# pcuETH.net
KiCad netlist of a schematic drawn in Altium Designer
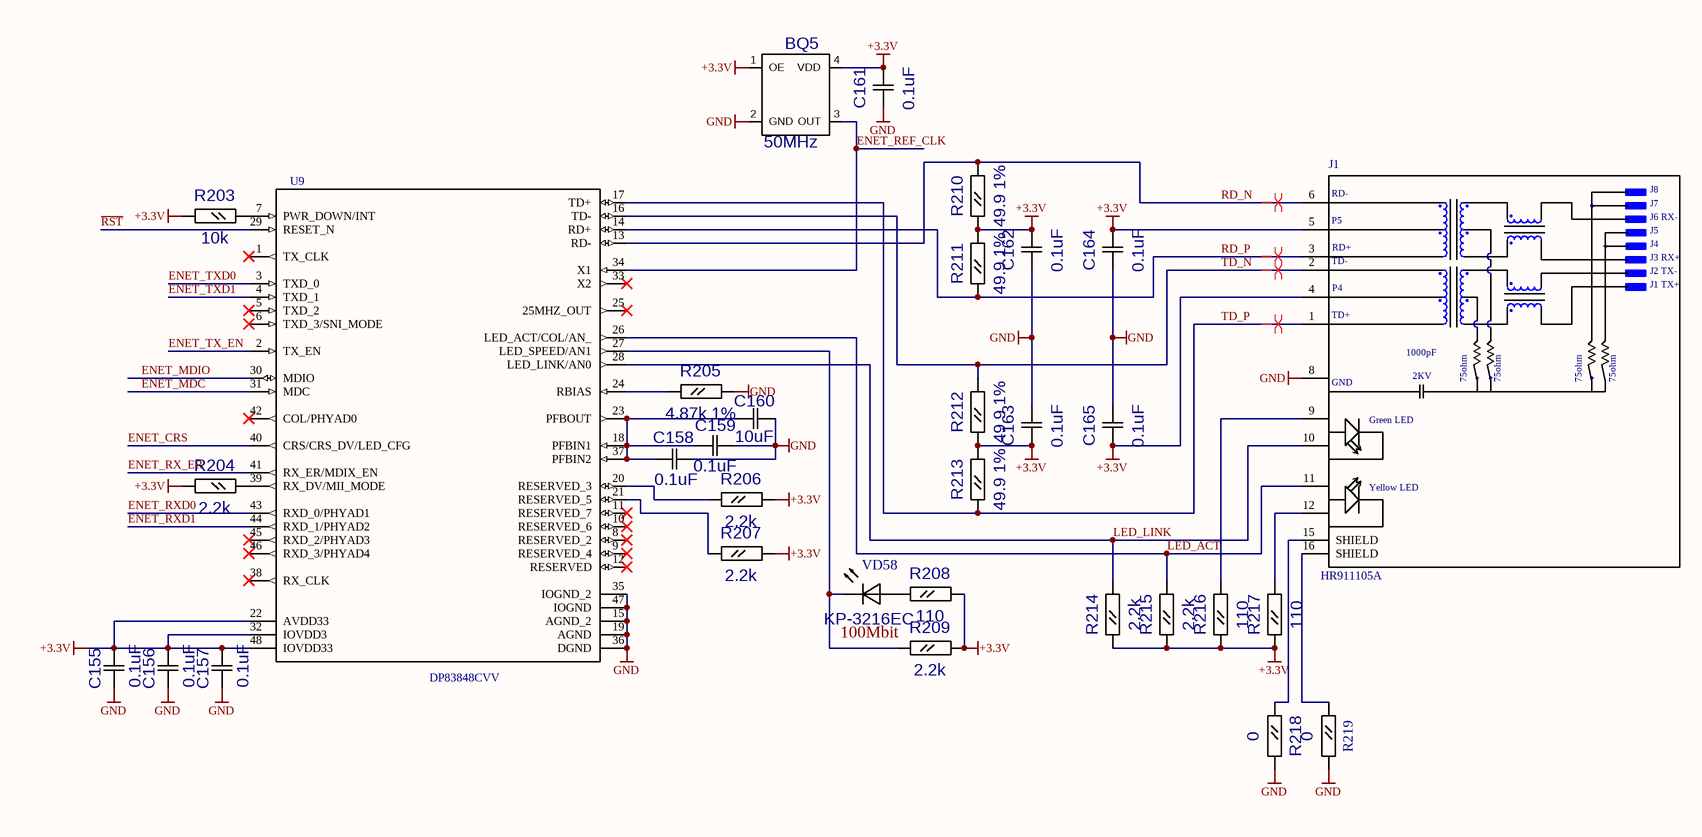
[diagram p0: pcuETH.SchDoc]

(export (version "E")
  (design (tool "Eeschema 10.0.6"))
  (components
    (comp (ref "BQ5") (value "50MHz") (footprint "FurmansLib:5032") (libsource (lib "Furmans") (part "OSC")))
    (comp (ref "C155")
      (value "0.1uF")
      (footprint "C0805")
      (description "C0805")
      (libsource (lib "FurmansLib") (part "C0805"))
    )
    (comp (ref "C156")
      (value "0.1uF")
      (footprint "C0805")
      (description "C0805")
      (libsource (lib "FurmansLib") (part "C0805"))
    )
    (comp (ref "C157")
      (value "0.1uF")
      (footprint "C0805")
      (description "C0805")
      (libsource (lib "FurmansLib") (part "C0805"))
    )
    (comp (ref "C158")
      (value "0.1uF")
      (footprint "C0805")
      (description "C0805")
      (libsource (lib "FurmansLib") (part "C0805"))
    )
    (comp (ref "C159")
      (value "0.1uF")
      (footprint "C0805")
      (description "C0805")
      (libsource (lib "FurmansLib") (part "C0805"))
    )
    (comp (ref "C160")
      (value "10uF")
      (footprint "C1206")
      (description "C1206")
      (libsource (lib "FurmansLib") (part "C1206"))
    )
    (comp (ref "C161")
      (value "0.1uF")
      (footprint "C0805")
      (description "C0805")
      (libsource (lib "FurmansLib") (part "C0805"))
    )
    (comp (ref "C162")
      (value "0.1uF")
      (footprint "C0805")
      (description "C0805")
      (libsource (lib "FurmansLib") (part "C0805"))
    )
    (comp (ref "C163")
      (value "0.1uF")
      (footprint "C0805")
      (description "C0805")
      (libsource (lib "FurmansLib") (part "C0805"))
    )
    (comp (ref "C164")
      (value "0.1uF")
      (footprint "C0805")
      (description "C0805")
      (libsource (lib "FurmansLib") (part "C0805"))
    )
    (comp (ref "C165")
      (value "0.1uF")
      (footprint "C0805")
      (description "C0805")
      (libsource (lib "FurmansLib") (part "C0805"))
    )
    (comp (ref "J1")
      (value "HR911105A")
      (footprint "HANRUN_HR911105A")
      (description "DIP RJ45 Connector;")
      (fields (field (name "MF") "HanRun"))
      (libsource (lib "FurmansLib") (part "HR911105A"))
    )
    (comp (ref "R203")
      (value "10k")
      (footprint "R0805")
      (description "R0805")
      (libsource (lib "FurmansLib") (part "R0805"))
    )
    (comp (ref "R204")
      (value "2.2k")
      (footprint "R0805")
      (description "R0805")
      (libsource (lib "FurmansLib") (part "R0805"))
    )
    (comp (ref "R205")
      (value "4.87k 1%")
      (footprint "R0805")
      (description "R0805")
      (libsource (lib "FurmansLib") (part "R0805"))
    )
    (comp (ref "R206")
      (value "2.2k")
      (footprint "R0805")
      (description "R0805")
      (libsource (lib "FurmansLib") (part "R0805"))
    )
    (comp (ref "R207")
      (value "2.2k")
      (footprint "R0805")
      (description "R0805")
      (libsource (lib "FurmansLib") (part "R0805"))
    )
    (comp (ref "R208")
      (value "110")
      (footprint "R0805")
      (description "R0805")
      (libsource (lib "FurmansLib") (part "R0805"))
    )
    (comp (ref "R209")
      (value "2.2k")
      (footprint "R0805")
      (description "R0805")
      (libsource (lib "FurmansLib") (part "R0805"))
    )
    (comp (ref "R210")
      (value "49.9 1%")
      (footprint "R0805")
      (description "R0805")
      (libsource (lib "FurmansLib") (part "R0805"))
    )
    (comp (ref "R211")
      (value "49.9 1%")
      (footprint "R0805")
      (description "R0805")
      (libsource (lib "FurmansLib") (part "R0805"))
    )
    (comp (ref "R212")
      (value "49.9 1%")
      (footprint "R0805")
      (description "R0805")
      (libsource (lib "FurmansLib") (part "R0805"))
    )
    (comp (ref "R213")
      (value "49.9 1%")
      (footprint "R0805")
      (description "R0805")
      (libsource (lib "FurmansLib") (part "R0805"))
    )
    (comp (ref "R214")
      (value "2.2k")
      (footprint "R0805")
      (description "R0805")
      (libsource (lib "FurmansLib") (part "R0805"))
    )
    (comp (ref "R215")
      (value "2.2k")
      (footprint "R0805")
      (description "R0805")
      (libsource (lib "FurmansLib") (part "R0805"))
    )
    (comp (ref "R216")
      (value "110")
      (footprint "R0805")
      (description "R0805")
      (libsource (lib "FurmansLib") (part "R0805"))
    )
    (comp (ref "R217")
      (value "110")
      (footprint "R0805")
      (description "R0805")
      (libsource (lib "FurmansLib") (part "R0805"))
    )
    (comp (ref "R218")
      (value "0")
      (footprint "R0805")
      (description "R0805")
      (libsource (lib "FurmansLib") (part "R0805"))
    )
    (comp (ref "R219")
      (value "0")
      (footprint "R0805")
      (description "R0805")
      (libsource (lib "FurmansLib") (part "R0805"))
    )
    (comp (ref "U9")
      (value "DP83848CVV")
      (footprint "QFP48")
      (fields
        (field (name "DIGI-KEY_PART_NUMBER") "DP83848CVV/NOPB-ND")
        (field (name "MF") "Texas Instruments")
        (field (name "MP") "DP83848CVV/NOPB")
      )
      (libsource (lib "FurmansLib") (part "DP83848CVV"))
    )
    (comp (ref "VD58")
      (value "KP-3216EC")
      (footprint "KP-3216 Hole")
      (libsource (lib "FurmansLib") (part "KP-3216EC"))
    )
  )
  (nets
    (net (code "1") (name "+3.3V") (class "Default")
      (node (ref "BQ5") (pin "1") (pinfunction "OE_1") (pintype "power_in"))
      (node (ref "BQ5") (pin "4") (pinfunction "VDD_4") (pintype "power_in"))
      (node (ref "C155") (pin "2") (pintype "passive"))
      (node (ref "C156") (pin "2") (pintype "passive"))
      (node (ref "C157") (pin "2") (pintype "passive"))
      (node (ref "C161") (pin "2") (pintype "passive"))
      (node (ref "C162") (pin "2") (pintype "passive"))
      (node (ref "C163") (pin "1") (pintype "passive"))
      (node (ref "C164") (pin "2") (pintype "passive"))
      (node (ref "C165") (pin "1") (pintype "passive"))
      (node (ref "J1") (pin "4") (pinfunction "P4_4") (pintype "passive"))
      (node (ref "J1") (pin "5") (pinfunction "P5_5") (pintype "passive"))
      (node (ref "R203") (pin "1") (pintype "passive"))
      (node (ref "R204") (pin "1") (pintype "passive"))
      (node (ref "R206") (pin "1") (pintype "passive"))
      (node (ref "R207") (pin "1") (pintype "passive"))
      (node (ref "R208") (pin "1") (pintype "passive"))
      (node (ref "R209") (pin "1") (pintype "passive"))
      (node (ref "R210") (pin "2") (pintype "passive"))
      (node (ref "R211") (pin "1") (pintype "passive"))
      (node (ref "R212") (pin "2") (pintype "passive"))
      (node (ref "R213") (pin "1") (pintype "passive"))
      (node (ref "R214") (pin "2") (pintype "passive"))
      (node (ref "R215") (pin "2") (pintype "passive"))
      (node (ref "R216") (pin "2") (pintype "passive"))
      (node (ref "R217") (pin "2") (pintype "passive"))
      (node (ref "U9") (pin "22") (pinfunction "AVDD33_22") (pintype "power_in"))
      (node (ref "U9") (pin "32") (pinfunction "IOVDD3_32") (pintype "power_in"))
      (node (ref "U9") (pin "48") (pinfunction "IOVDD33_48") (pintype "power_in"))
    )
    (net (code "2") (name "/ENET_CRS") (class "Default")
      (node (ref "U9") (pin "40") (pinfunction "CRS/CRS_DV/LED_CFG_40") (pintype "output"))
    )
    (net (code "3") (name "/ENET_MDC") (class "Default")
      (node (ref "U9") (pin "31") (pinfunction "MDC_31") (pintype "input"))
    )
    (net (code "4") (name "/ENET_MDIO") (class "Default")
      (node (ref "U9") (pin "30") (pinfunction "MDIO_30") (pintype "bidirectional"))
    )
    (net (code "5") (name "/ENET_REF_CLK") (class "Default")
      (node (ref "BQ5") (pin "3") (pinfunction "OUT_3") (pintype "power_in"))
      (node (ref "U9") (pin "34") (pinfunction "X1_34") (pintype "input"))
    )
    (net (code "6") (name "/ENET_RXD0") (class "Default")
      (node (ref "U9") (pin "43") (pinfunction "RXD_0/PHYAD1_43") (pintype "output"))
    )
    (net (code "7") (name "/ENET_RXD1") (class "Default")
      (node (ref "U9") (pin "44") (pinfunction "RXD_1/PHYAD2_44") (pintype "output"))
    )
    (net (code "8") (name "/ENET_RX_ER") (class "Default")
      (node (ref "U9") (pin "41") (pinfunction "RX_ER/MDIX_EN_41") (pintype "output"))
    )
    (net (code "9") (name "/ENET_TXD0") (class "Default")
      (node (ref "U9") (pin "3") (pinfunction "TXD_0_3") (pintype "input"))
    )
    (net (code "10") (name "/ENET_TXD1") (class "Default")
      (node (ref "U9") (pin "4") (pinfunction "TXD_1_4") (pintype "input"))
    )
    (net (code "11") (name "/ENET_TX_EN") (class "Default")
      (node (ref "U9") (pin "2") (pinfunction "TX_EN_2") (pintype "input"))
    )
    (net (code "12") (name "/LED_ACT") (class "Default")
      (node (ref "J1") (pin "11") (pinfunction "YA_11") (pintype "passive"))
      (node (ref "R215") (pin "1") (pintype "passive"))
      (node (ref "U9") (pin "26") (pinfunction "LED_ACT/COL/AN__26") (pintype "output"))
    )
    (net (code "13") (name "/LED_LINK") (class "Default")
      (node (ref "J1") (pin "10") (pinfunction "GC_10") (pintype "passive"))
      (node (ref "R214") (pin "1") (pintype "passive"))
      (node (ref "U9") (pin "28") (pinfunction "LED_LINK/AN0_28") (pintype "output"))
    )
    (net (code "14") (name "/RD_N") (class "Default")
      (node (ref "J1") (pin "6") (pinfunction "RD-_6") (pintype "passive"))
      (node (ref "R210") (pin "1") (pintype "passive"))
      (node (ref "U9") (pin "13") (pinfunction "RD-_13") (pintype "bidirectional"))
    )
    (net (code "15") (name "/RD_P") (class "Default")
      (node (ref "J1") (pin "3") (pinfunction "RD+_3") (pintype "passive"))
      (node (ref "R211") (pin "2") (pintype "passive"))
      (node (ref "U9") (pin "14") (pinfunction "RD+_14") (pintype "bidirectional"))
    )
    (net (code "16") (name "/TD_N") (class "Default")
      (node (ref "J1") (pin "2") (pinfunction "TD-_2") (pintype "passive"))
      (node (ref "R212") (pin "1") (pintype "passive"))
      (node (ref "U9") (pin "16") (pinfunction "TD-_16") (pintype "bidirectional"))
    )
    (net (code "17") (name "/TD_P") (class "Default")
      (node (ref "J1") (pin "1") (pinfunction "TD+_1") (pintype "passive"))
      (node (ref "R213") (pin "2") (pintype "passive"))
      (node (ref "U9") (pin "17") (pinfunction "TD+_17") (pintype "bidirectional"))
    )
    (net (code "18") (name "/~{RST}") (class "Default")
      (node (ref "U9") (pin "29") (pinfunction "RESET_N_29") (pintype "input"))
    )
    (net (code "19") (name "GND") (class "Default")
      (node (ref "BQ5") (pin "2") (pinfunction "GND_2") (pintype "power_in"))
      (node (ref "C155") (pin "1") (pintype "passive"))
      (node (ref "C156") (pin "1") (pintype "passive"))
      (node (ref "C157") (pin "1") (pintype "passive"))
      (node (ref "C158") (pin "2") (pintype "passive"))
      (node (ref "C159") (pin "2") (pintype "passive"))
      (node (ref "C160") (pin "2") (pintype "passive"))
      (node (ref "C161") (pin "1") (pintype "passive"))
      (node (ref "C162") (pin "1") (pintype "passive"))
      (node (ref "C163") (pin "2") (pintype "passive"))
      (node (ref "C164") (pin "1") (pintype "passive"))
      (node (ref "C165") (pin "2") (pintype "passive"))
      (node (ref "J1") (pin "8") (pinfunction "GND_8") (pintype "power_in"))
      (node (ref "R205") (pin "1") (pintype "passive"))
      (node (ref "R218") (pin "1") (pintype "passive"))
      (node (ref "R219") (pin "1") (pintype "passive"))
      (node (ref "U9") (pin "15") (pinfunction "AGND_2_15") (pintype "passive"))
      (node (ref "U9") (pin "19") (pinfunction "AGND_19") (pintype "passive"))
      (node (ref "U9") (pin "35") (pinfunction "IOGND_2_35") (pintype "passive"))
      (node (ref "U9") (pin "36") (pinfunction "DGND_36") (pintype "passive"))
      (node (ref "U9") (pin "47") (pinfunction "IOGND_47") (pintype "passive"))
    )
    (net (code "20") (name "Net-(J1-GA)") (class "Default")
      (node (ref "J1") (pin "9") (pinfunction "GA_9") (pintype "passive"))
      (node (ref "R216") (pin "1") (pintype "passive"))
    )
    (net (code "21") (name "Net-(J1-SHIELD-Pad15)") (class "Default")
      (node (ref "J1") (pin "15") (pinfunction "SHIELD_15") (pintype "passive"))
      (node (ref "R218") (pin "2") (pintype "passive"))
    )
    (net (code "22") (name "Net-(J1-SHIELD-Pad16)") (class "Default")
      (node (ref "J1") (pin "16") (pinfunction "SHIELD_16") (pintype "passive"))
      (node (ref "R219") (pin "2") (pintype "passive"))
    )
    (net (code "23") (name "Net-(J1-YC)") (class "Default")
      (node (ref "J1") (pin "12") (pinfunction "YC_12") (pintype "passive"))
      (node (ref "R217") (pin "1") (pintype "passive"))
    )
    (net (code "24") (name "Net-(R208-Pad2)") (class "Default")
      (node (ref "R208") (pin "2") (pintype "passive"))
      (node (ref "VD58") (pin "1") (pintype "passive"))
    )
    (net (code "25") (name "Net-(U9-LED_SPEED{slash}AN1)") (class "Default")
      (node (ref "R209") (pin "2") (pintype "passive"))
      (node (ref "U9") (pin "27") (pinfunction "LED_SPEED/AN1_27") (pintype "output"))
      (node (ref "VD58") (pin "2") (pintype "passive"))
    )
    (net (code "26") (name "Net-(U9-PFBIN1)") (class "Default")
      (node (ref "C158") (pin "1") (pintype "passive"))
      (node (ref "C159") (pin "1") (pintype "passive"))
      (node (ref "C160") (pin "1") (pintype "passive"))
      (node (ref "U9") (pin "18") (pinfunction "PFBIN1_18") (pintype "input"))
      (node (ref "U9") (pin "23") (pinfunction "PFBOUT_23") (pintype "output"))
      (node (ref "U9") (pin "37") (pinfunction "PFBIN2_37") (pintype "input"))
    )
    (net (code "27") (name "Net-(U9-PWR_DOWN{slash}INT)") (class "Default")
      (node (ref "R203") (pin "2") (pintype "passive"))
      (node (ref "U9") (pin "7") (pinfunction "PWR_DOWN/INT_7") (pintype "input"))
    )
    (net (code "28") (name "Net-(U9-RBIAS)") (class "Default")
      (node (ref "R205") (pin "2") (pintype "passive"))
      (node (ref "U9") (pin "24") (pinfunction "RBIAS_24") (pintype "input"))
    )
    (net (code "29") (name "Net-(U9-RESERVED_3)") (class "Default")
      (node (ref "R206") (pin "2") (pintype "passive"))
      (node (ref "U9") (pin "20") (pinfunction "RESERVED_3_20") (pintype "bidirectional"))
    )
    (net (code "30") (name "Net-(U9-RESERVED_5)") (class "Default")
      (node (ref "R207") (pin "2") (pintype "passive"))
      (node (ref "U9") (pin "21") (pinfunction "RESERVED_5_21") (pintype "bidirectional"))
    )
    (net (code "31") (name "Net-(U9-RX_DV{slash}MII_MODE)") (class "Default")
      (node (ref "R204") (pin "2") (pintype "passive"))
      (node (ref "U9") (pin "39") (pinfunction "RX_DV/MII_MODE_39") (pintype "output"))
    )
    (net (code "32") (name "unconnected-(U9-25MHZ_OUT-Pad25)") (class "Default")
      (node (ref "U9") (pin "25") (pinfunction "25MHZ_OUT_25") (pintype "output+no_connect"))
    )
    (net (code "33") (name "unconnected-(U9-COL{slash}PHYAD0-Pad42)") (class "Default")
      (node (ref "U9") (pin "42") (pinfunction "COL/PHYAD0_42") (pintype "output+no_connect"))
    )
    (net (code "34") (name "unconnected-(U9-RESERVED-Pad12)") (class "Default")
      (node (ref "U9") (pin "12") (pinfunction "RESERVED_12") (pintype "bidirectional+no_connect"))
    )
    (net (code "35") (name "unconnected-(U9-RESERVED_2-Pad8)") (class "Default")
      (node (ref "U9") (pin "8") (pinfunction "RESERVED_2_8") (pintype "bidirectional+no_connect"))
    )
    (net (code "36") (name "unconnected-(U9-RESERVED_4-Pad9)") (class "Default")
      (node (ref "U9") (pin "9") (pinfunction "RESERVED_4_9") (pintype "bidirectional+no_connect"))
    )
    (net (code "37") (name "unconnected-(U9-RESERVED_6-Pad10)") (class "Default")
      (node (ref "U9") (pin "10") (pinfunction "RESERVED_6_10") (pintype "bidirectional+no_connect"))
    )
    (net (code "38") (name "unconnected-(U9-RESERVED_7-Pad11)") (class "Default")
      (node (ref "U9") (pin "11") (pinfunction "RESERVED_7_11") (pintype "bidirectional+no_connect"))
    )
    (net (code "39") (name "unconnected-(U9-RXD_2{slash}PHYAD3-Pad45)") (class "Default")
      (node (ref "U9") (pin "45") (pinfunction "RXD_2/PHYAD3_45") (pintype "output+no_connect"))
    )
    (net (code "40") (name "unconnected-(U9-RXD_3{slash}PHYAD4-Pad46)") (class "Default")
      (node (ref "U9") (pin "46") (pinfunction "RXD_3/PHYAD4_46") (pintype "output+no_connect"))
    )
    (net (code "41") (name "unconnected-(U9-RX_CLK-Pad38)") (class "Default")
      (node (ref "U9") (pin "38") (pinfunction "RX_CLK_38") (pintype "output+no_connect"))
    )
    (net (code "42") (name "unconnected-(U9-TXD_2-Pad5)") (class "Default")
      (node (ref "U9") (pin "5") (pinfunction "TXD_2_5") (pintype "input+no_connect"))
    )
    (net (code "43") (name "unconnected-(U9-TXD_3{slash}SNI_MODE-Pad6)") (class "Default")
      (node (ref "U9") (pin "6") (pinfunction "TXD_3/SNI_MODE_6") (pintype "input+no_connect"))
    )
    (net (code "44") (name "unconnected-(U9-TX_CLK-Pad1)") (class "Default")
      (node (ref "U9") (pin "1") (pinfunction "TX_CLK_1") (pintype "output+no_connect"))
    )
    (net (code "45") (name "unconnected-(U9-X2-Pad33)") (class "Default")
      (node (ref "U9") (pin "33") (pinfunction "X2_33") (pintype "output+no_connect"))
    )
  )
)
